# data_proV2.net
KiCad netlist of a schematic drawn in EAGLE
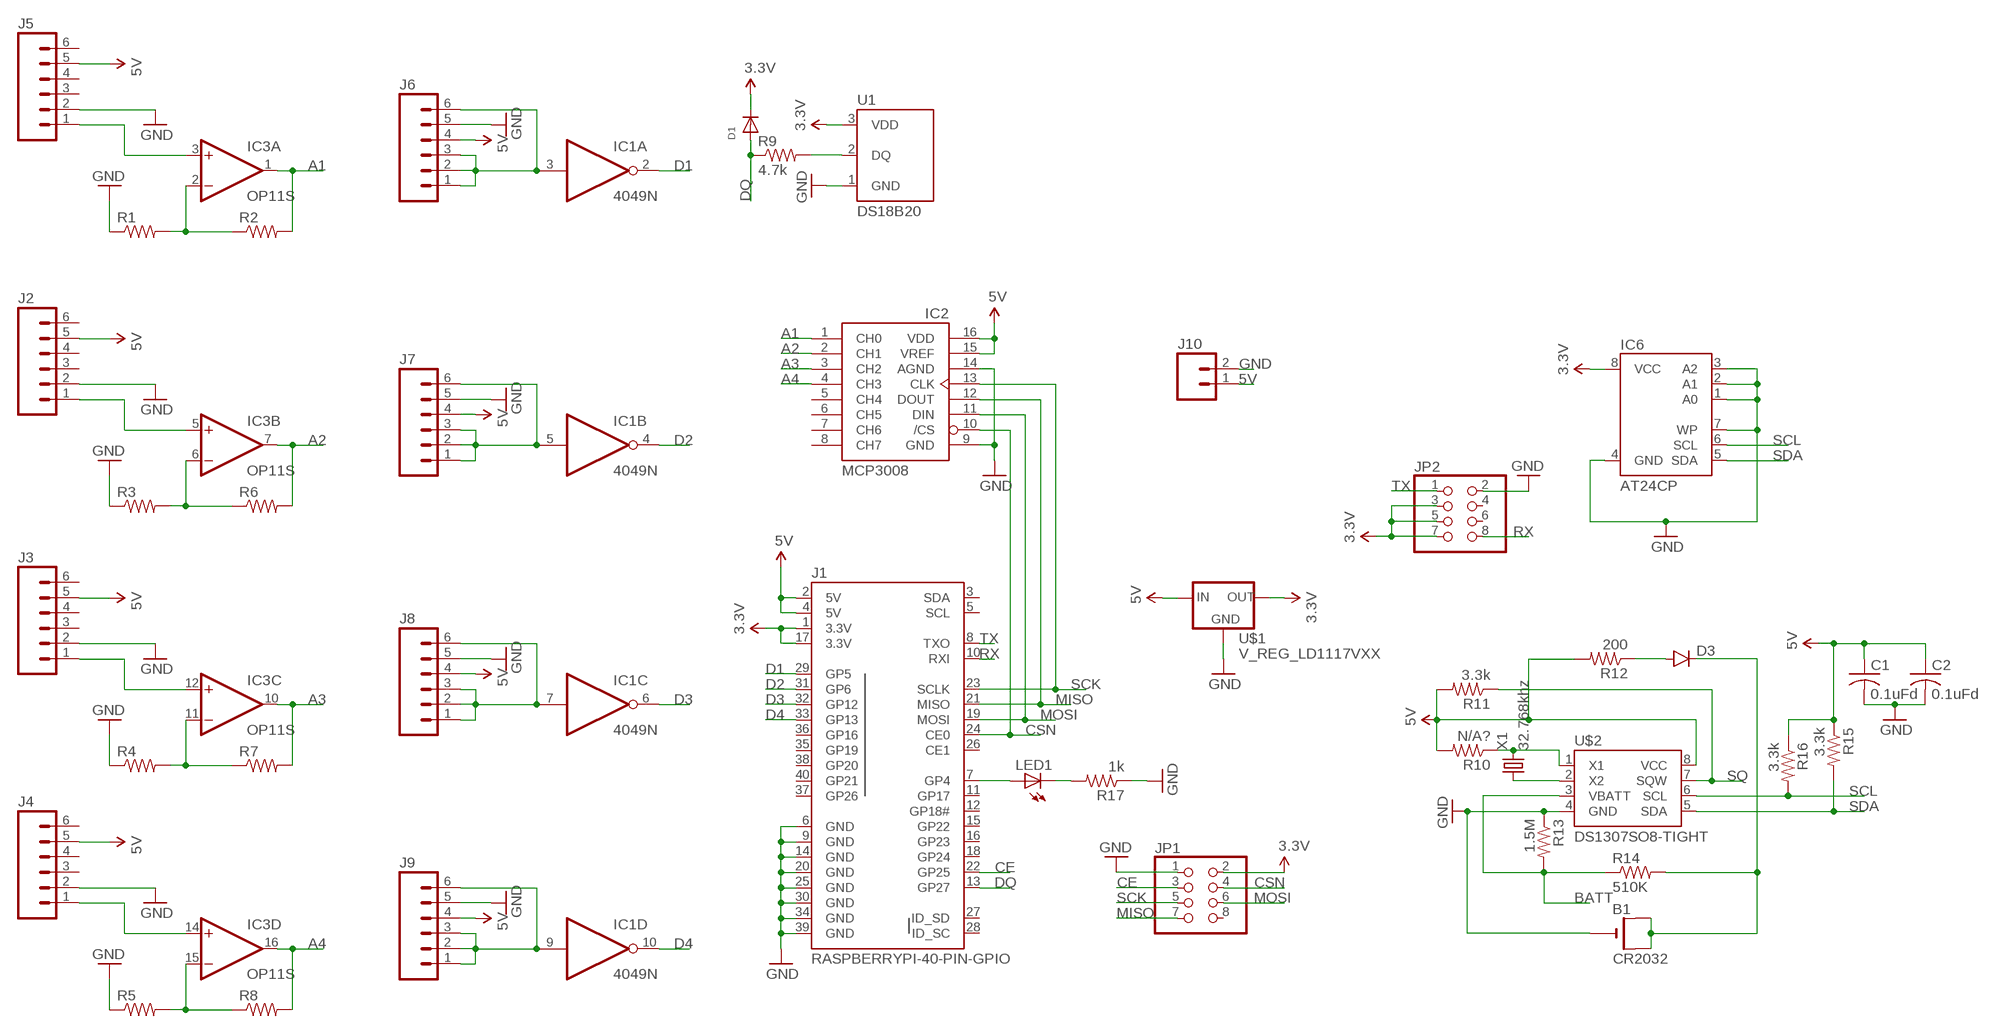
[diagram p0: schematic, sheet 1]

(export (version "E")
  (design (tool "Eeschema 10.0.6"))
  (components
    (comp (ref "B1")
      (value "CR2032")
      (footprint "eagle-import:CR2032-SMD")
      (libsource (lib "eagle-import") (part "CR2032SMT"))
    )
    (comp (ref "C1")
      (value "0.1uFd")
      (footprint "eagle-import:C0805")
      (libsource (lib "eagle-import") (part "C-USC0805"))
    )
    (comp (ref "C2")
      (value "0.1uFd")
      (footprint "eagle-import:C0805")
      (libsource (lib "eagle-import") (part "C-USC0805"))
    )
    (comp (ref "D1")
      (value "DIODESOD-323F")
      (footprint "eagle-import:SOD-323F")
      (libsource (lib "eagle-import") (part "DIODESOD-323F"))
    )
    (comp (ref "D3")
      (value "DIODESMB")
      (footprint "eagle-import:SMB-DIODE")
      (libsource (lib "eagle-import") (part "DIODESMB"))
    )
    (comp (ref "IC1")
      (value "4049N")
      (footprint "eagle-import:DIL16")
      (libsource (lib "eagle-import") (part "4049N"))
    )
    (comp (ref "IC2")
      (value "MCP3008")
      (footprint "eagle-import:DIL16")
      (libsource (lib "eagle-import") (part "MCP3008"))
    )
    (comp (ref "IC3")
      (value "OP11S")
      (footprint "eagle-import:DIL16")
      (libsource (lib "eagle-import") (part "OP11S"))
    )
    (comp (ref "IC6")
      (value "AT24CP")
      (footprint "eagle-import:DIL08")
      (fields (field (name "MPN") "AT24C1024BW-SH-B"))
      (libsource (lib "eagle-import") (part "AT24CP"))
    )
    (comp (ref "J1")
      (value "RASPBERRYPI-40-PIN-GPIO")
      (footprint "eagle-import:2X20-SHROUDED")
      (libsource (lib "eagle-import") (part "RASPBERRYPI-40-PIN-GPIO"))
    )
    (comp (ref "J2")
      (value "M06VERNIER-ANALOG")
      (footprint "eagle-import:BTA")
      (libsource (lib "eagle-import") (part "M06VERNIER-ANALOG"))
    )
    (comp (ref "J3")
      (value "M06VERNIER-ANALOG")
      (footprint "eagle-import:BTA")
      (libsource (lib "eagle-import") (part "M06VERNIER-ANALOG"))
    )
    (comp (ref "J4")
      (value "M06VERNIER-ANALOG")
      (footprint "eagle-import:BTA")
      (libsource (lib "eagle-import") (part "M06VERNIER-ANALOG"))
    )
    (comp (ref "J5")
      (value "M06VERNIER-ANALOG")
      (footprint "eagle-import:BTA")
      (libsource (lib "eagle-import") (part "M06VERNIER-ANALOG"))
    )
    (comp (ref "J6")
      (value "M06VERNIER-DIGITAL")
      (footprint "eagle-import:BTD")
      (libsource (lib "eagle-import") (part "M06VERNIER-DIGITAL"))
    )
    (comp (ref "J7")
      (value "M06VERNIER-DIGITAL")
      (footprint "eagle-import:BTD")
      (libsource (lib "eagle-import") (part "M06VERNIER-DIGITAL"))
    )
    (comp (ref "J8")
      (value "M06VERNIER-DIGITAL")
      (footprint "eagle-import:BTD")
      (libsource (lib "eagle-import") (part "M06VERNIER-DIGITAL"))
    )
    (comp (ref "J9")
      (value "M06VERNIER-DIGITAL")
      (footprint "eagle-import:BTD")
      (libsource (lib "eagle-import") (part "M06VERNIER-DIGITAL"))
    )
    (comp (ref "J10")
      (value "M02PTH")
      (footprint "eagle-import:1X02")
      (libsource (lib "eagle-import") (part "M02PTH"))
    )
    (comp (ref "JP1")
      (value "PINHD-2X4")
      (footprint "eagle-import:2X04")
      (libsource (lib "eagle-import") (part "pinhead_PINHD-2X4"))
    )
    (comp (ref "JP2")
      (value "PINHD-2X4")
      (footprint "eagle-import:2X04")
      (libsource (lib "eagle-import") (part "PINHD-2X4"))
    )
    (comp (ref "LED1")
      (value "LEDCHIP-LED0805")
      (footprint "eagle-import:CHIP-LED0805")
      (libsource (lib "eagle-import") (part "LEDCHIP-LED0805"))
    )
    (comp (ref "R1")
      (value "R-US_R0805")
      (footprint "eagle-import:R0805")
      (libsource (lib "eagle-import") (part "resistor_R-US_R0805"))
    )
    (comp (ref "R2")
      (value "R-US_R0805")
      (footprint "eagle-import:R0805")
      (libsource (lib "eagle-import") (part "resistor_R-US_R0805"))
    )
    (comp (ref "R3")
      (value "R-US_R0805")
      (footprint "eagle-import:R0805")
      (libsource (lib "eagle-import") (part "resistor_R-US_R0805"))
    )
    (comp (ref "R4")
      (value "R-US_R0805")
      (footprint "eagle-import:R0805")
      (libsource (lib "eagle-import") (part "resistor_R-US_R0805"))
    )
    (comp (ref "R5")
      (value "R-US_R0805")
      (footprint "eagle-import:R0805")
      (libsource (lib "eagle-import") (part "resistor_R-US_R0805"))
    )
    (comp (ref "R6")
      (value "R-US_R0805")
      (footprint "eagle-import:R0805")
      (libsource (lib "eagle-import") (part "resistor_R-US_R0805"))
    )
    (comp (ref "R7")
      (value "R-US_R0805")
      (footprint "eagle-import:R0805")
      (libsource (lib "eagle-import") (part "resistor_R-US_R0805"))
    )
    (comp (ref "R8")
      (value "R-US_R0805")
      (footprint "eagle-import:R0805")
      (libsource (lib "eagle-import") (part "resistor_R-US_R0805"))
    )
    (comp (ref "R9")
      (value "4.7k")
      (footprint "eagle-import:R0805")
      (libsource (lib "eagle-import") (part "resistor_R-US_R0805"))
    )
    (comp (ref "R10")
      (value "N/A?")
      (footprint "eagle-import:R0805")
      (libsource (lib "eagle-import") (part "R-US_R0805"))
    )
    (comp (ref "R11")
      (value "3.3k")
      (footprint "eagle-import:R0805")
      (libsource (lib "eagle-import") (part "R-US_R0805"))
    )
    (comp (ref "R12")
      (value "200")
      (footprint "eagle-import:R0805")
      (libsource (lib "eagle-import") (part "R-US_R0805"))
    )
    (comp (ref "R13")
      (value "1.5M")
      (footprint "eagle-import:R0805")
      (libsource (lib "eagle-import") (part "R-US_R0805"))
    )
    (comp (ref "R14")
      (value "510K")
      (footprint "eagle-import:R0805")
      (libsource (lib "eagle-import") (part "R-US_R0805"))
    )
    (comp (ref "R15")
      (value "3.3k")
      (footprint "eagle-import:R0805")
      (libsource (lib "eagle-import") (part "R-US_R0805"))
    )
    (comp (ref "R16")
      (value "3.3k")
      (footprint "eagle-import:R0805")
      (libsource (lib "eagle-import") (part "R-US_R0805"))
    )
    (comp (ref "R17")
      (value "1k")
      (footprint "eagle-import:R0805")
      (libsource (lib "eagle-import") (part "R-US_R0805"))
    )
    (comp (ref "U$1")
      (value "V_REG_LD1117VXX")
      (footprint "eagle-import:78XXL")
      (libsource (lib "eagle-import") (part "V_REG_LD1117VXX"))
    )
    (comp (ref "U$2")
      (value "DS1307SO8-TIGHT")
      (footprint "eagle-import:SO08-TIGHT")
      (libsource (lib "eagle-import") (part "DS1307SO8-TIGHT"))
    )
    (comp (ref "U1")
      (value "DS18B20")
      (footprint "eagle-import:TO-92-AMMO")
      (libsource (lib "eagle-import") (part "DS18B20"))
    )
    (comp (ref "X1")
      (value "32.768khz")
      (footprint "eagle-import:TC38H")
      (libsource (lib "eagle-import") (part "CRYSTALTC38H"))
    )
  )
  (nets
    (net (code "1") (name "/A1") (class "Default")
      (node (ref "IC2") (pin "1") (pinfunction "CH0_1") (pintype "input"))
      (node (ref "IC3") (pin "1") (pinfunction "OUT_1") (pintype "output"))
      (node (ref "R2") (pin "2") (pinfunction "2_2") (pintype "passive"))
    )
    (net (code "2") (name "/A2") (class "Default")
      (node (ref "IC2") (pin "2") (pinfunction "CH1_2") (pintype "input"))
      (node (ref "IC3") (pin "7") (pinfunction "OUT_7") (pintype "output"))
      (node (ref "R6") (pin "2") (pinfunction "2_2") (pintype "passive"))
    )
    (net (code "3") (name "/A3") (class "Default")
      (node (ref "IC2") (pin "3") (pinfunction "CH2_3") (pintype "input"))
      (node (ref "IC3") (pin "10") (pinfunction "OUT_10") (pintype "output"))
      (node (ref "R7") (pin "2") (pinfunction "2_2") (pintype "passive"))
    )
    (net (code "4") (name "/A4") (class "Default")
      (node (ref "IC2") (pin "4") (pinfunction "CH3_4") (pintype "input"))
      (node (ref "IC3") (pin "16") (pinfunction "OUT_16") (pintype "output"))
      (node (ref "R8") (pin "2") (pinfunction "2_2") (pintype "passive"))
    )
    (net (code "5") (name "/BATT") (class "Default")
      (node (ref "R13") (pin "2") (pinfunction "2_2") (pintype "passive"))
      (node (ref "R14") (pin "1") (pinfunction "1_1") (pintype "passive"))
      (node (ref "U$2") (pin "3") (pinfunction "VBATT_3") (pintype "bidirectional"))
    )
    (net (code "6") (name "/CE") (class "Default")
      (node (ref "J1") (pin "22") (pinfunction "GP25_22") (pintype "bidirectional"))
      (node (ref "JP1") (pin "3") (pinfunction "3_3") (pintype "passive"))
    )
    (net (code "7") (name "/CSN") (class "Default")
      (node (ref "IC2") (pin "10") (pinfunction "/CS_10") (pintype "input"))
      (node (ref "J1") (pin "24") (pinfunction "CE0_24") (pintype "output"))
      (node (ref "JP1") (pin "4") (pinfunction "4_4") (pintype "passive"))
    )
    (net (code "8") (name "/D1") (class "Default")
      (node (ref "IC1") (pin "2") (pinfunction "O_2") (pintype "output"))
      (node (ref "J1") (pin "29") (pinfunction "GP5_29") (pintype "bidirectional"))
    )
    (net (code "9") (name "/D2") (class "Default")
      (node (ref "IC1") (pin "4") (pinfunction "O_4") (pintype "output"))
      (node (ref "J1") (pin "31") (pinfunction "GP6_31") (pintype "bidirectional"))
    )
    (net (code "10") (name "/D3") (class "Default")
      (node (ref "IC1") (pin "6") (pinfunction "O_6") (pintype "output"))
      (node (ref "J1") (pin "32") (pinfunction "GP12_32") (pintype "bidirectional"))
    )
    (net (code "11") (name "/D4") (class "Default")
      (node (ref "IC1") (pin "10") (pinfunction "O_10") (pintype "output"))
      (node (ref "J1") (pin "33") (pinfunction "GP13_33") (pintype "bidirectional"))
    )
    (net (code "12") (name "/DQ") (class "Default")
      (node (ref "D1") (pin "A") (pinfunction "A_A") (pintype "passive"))
      (node (ref "J1") (pin "13") (pinfunction "GP27_13") (pintype "bidirectional"))
      (node (ref "R9") (pin "1") (pinfunction "1_1") (pintype "passive"))
    )
    (net (code "13") (name "/MISO") (class "Default")
      (node (ref "IC2") (pin "12") (pinfunction "DOUT_12") (pintype "output"))
      (node (ref "J1") (pin "21") (pinfunction "MISO_21") (pintype "input"))
      (node (ref "JP1") (pin "7") (pinfunction "7_7") (pintype "passive"))
    )
    (net (code "14") (name "/MOSI") (class "Default")
      (node (ref "IC2") (pin "11") (pinfunction "DIN_11") (pintype "input"))
      (node (ref "J1") (pin "19") (pinfunction "MOSI_19") (pintype "output"))
      (node (ref "JP1") (pin "6") (pinfunction "6_6") (pintype "passive"))
    )
    (net (code "15") (name "/RX") (class "Default")
      (node (ref "J1") (pin "10") (pinfunction "RXI_10") (pintype "input"))
      (node (ref "JP2") (pin "8") (pinfunction "8_8") (pintype "passive"))
    )
    (net (code "16") (name "/SCK") (class "Default")
      (node (ref "IC2") (pin "13") (pinfunction "CLK_13") (pintype "input"))
      (node (ref "J1") (pin "23") (pinfunction "SCLK_23") (pintype "output"))
      (node (ref "JP1") (pin "5") (pinfunction "5_5") (pintype "passive"))
    )
    (net (code "17") (name "/SCL") (class "Default")
      (node (ref "IC6") (pin "6") (pinfunction "SCL_6") (pintype "bidirectional"))
      (node (ref "R16") (pin "2") (pinfunction "2_2") (pintype "passive"))
      (node (ref "U$2") (pin "6") (pinfunction "SCL_6") (pintype "bidirectional"))
    )
    (net (code "18") (name "/SDA") (class "Default")
      (node (ref "IC6") (pin "5") (pinfunction "SDA_5") (pintype "bidirectional"))
      (node (ref "R15") (pin "2") (pinfunction "2_2") (pintype "passive"))
      (node (ref "U$2") (pin "5") (pinfunction "SDA_5") (pintype "bidirectional"))
    )
    (net (code "19") (name "/SQ") (class "Default")
      (node (ref "R11") (pin "1") (pinfunction "1_1") (pintype "passive"))
      (node (ref "U$2") (pin "7") (pinfunction "SQW_7") (pintype "bidirectional"))
    )
    (net (code "20") (name "/TX") (class "Default")
      (node (ref "J1") (pin "8") (pinfunction "TXO_8") (pintype "output"))
      (node (ref "JP2") (pin "1") (pinfunction "1_1") (pintype "passive"))
    )
    (net (code "21") (name "3.3V") (class "Default")
      (node (ref "D1") (pin "C") (pinfunction "C_C") (pintype "passive"))
      (node (ref "IC6") (pin "8") (pinfunction "VCC_8") (pintype "power_in"))
      (node (ref "J1") (pin "1") (pinfunction "3.3V_1") (pintype "power_in"))
      (node (ref "J1") (pin "17") (pinfunction "3.3V_17") (pintype "power_in"))
      (node (ref "JP1") (pin "2") (pinfunction "2_2") (pintype "passive"))
      (node (ref "JP2") (pin "3") (pinfunction "3_3") (pintype "passive"))
      (node (ref "JP2") (pin "5") (pinfunction "5_5") (pintype "passive"))
      (node (ref "JP2") (pin "7") (pinfunction "7_7") (pintype "passive"))
      (node (ref "U$1") (pin "GND") (pinfunction "OUT_GND") (pintype "passive"))
      (node (ref "U1") (pin "3") (pinfunction "VDD_3") (pintype "power_in"))
    )
    (net (code "22") (name "5V") (class "Default")
      (node (ref "C1") (pin "1") (pinfunction "1_1") (pintype "passive"))
      (node (ref "C2") (pin "1") (pinfunction "1_1") (pintype "passive"))
      (node (ref "IC2") (pin "15") (pinfunction "VREF_15") (pintype "input"))
      (node (ref "IC2") (pin "16") (pinfunction "VDD_16") (pintype "power_in"))
      (node (ref "J1") (pin "2") (pinfunction "5V_2") (pintype "power_in"))
      (node (ref "J1") (pin "4") (pinfunction "5V_4") (pintype "power_in"))
      (node (ref "J10") (pin "1") (pinfunction "1_1") (pintype "passive"))
      (node (ref "J2") (pin "5") (pinfunction "5_5") (pintype "passive"))
      (node (ref "J3") (pin "5") (pinfunction "5_5") (pintype "passive"))
      (node (ref "J4") (pin "5") (pinfunction "5_5") (pintype "passive"))
      (node (ref "J5") (pin "5") (pinfunction "5_5") (pintype "passive"))
      (node (ref "J6") (pin "4") (pinfunction "4_4") (pintype "passive"))
      (node (ref "J7") (pin "4") (pinfunction "4_4") (pintype "passive"))
      (node (ref "J8") (pin "4") (pinfunction "4_4") (pintype "passive"))
      (node (ref "J9") (pin "4") (pinfunction "4_4") (pintype "passive"))
      (node (ref "R10") (pin "2") (pinfunction "2_2") (pintype "passive"))
      (node (ref "R11") (pin "2") (pinfunction "2_2") (pintype "passive"))
      (node (ref "R12") (pin "2") (pinfunction "2_2") (pintype "passive"))
      (node (ref "R15") (pin "1") (pinfunction "1_1") (pintype "passive"))
      (node (ref "R16") (pin "1") (pinfunction "1_1") (pintype "passive"))
      (node (ref "U$1") (pin "OUT") (pinfunction "IN_OUT") (pintype "input"))
      (node (ref "U$2") (pin "8") (pinfunction "VCC_8") (pintype "bidirectional"))
    )
    (net (code "23") (name "GND") (class "Default")
      (node (ref "B1") (pin "-") (pinfunction "-_-") (pintype "passive"))
      (node (ref "C1") (pin "2") (pinfunction "2_2") (pintype "passive"))
      (node (ref "C2") (pin "2") (pinfunction "2_2") (pintype "passive"))
      (node (ref "IC2") (pin "14") (pinfunction "AGND_14") (pintype "power_in"))
      (node (ref "IC2") (pin "9") (pinfunction "GND_9") (pintype "power_in"))
      (node (ref "IC6") (pin "1") (pinfunction "A0_1") (pintype "input"))
      (node (ref "IC6") (pin "2") (pinfunction "A1_2") (pintype "input"))
      (node (ref "IC6") (pin "3") (pinfunction "A2_3") (pintype "input"))
      (node (ref "IC6") (pin "4") (pinfunction "GND_4") (pintype "power_in"))
      (node (ref "IC6") (pin "7") (pinfunction "WP_7") (pintype "input"))
      (node (ref "J1") (pin "14") (pinfunction "GND_14") (pintype "power_in"))
      (node (ref "J1") (pin "20") (pinfunction "GND_20") (pintype "power_in"))
      (node (ref "J1") (pin "25") (pinfunction "GND_25") (pintype "power_in"))
      (node (ref "J1") (pin "30") (pinfunction "GND_30") (pintype "power_in"))
      (node (ref "J1") (pin "34") (pinfunction "GND_34") (pintype "power_in"))
      (node (ref "J1") (pin "39") (pinfunction "GND_39") (pintype "power_in"))
      (node (ref "J1") (pin "6") (pinfunction "GND_6") (pintype "power_in"))
      (node (ref "J1") (pin "9") (pinfunction "GND_9") (pintype "power_in"))
      (node (ref "J10") (pin "2") (pinfunction "2_2") (pintype "passive"))
      (node (ref "J2") (pin "2") (pinfunction "2_2") (pintype "passive"))
      (node (ref "J3") (pin "2") (pinfunction "2_2") (pintype "passive"))
      (node (ref "J4") (pin "2") (pinfunction "2_2") (pintype "passive"))
      (node (ref "J5") (pin "2") (pinfunction "2_2") (pintype "passive"))
      (node (ref "J6") (pin "5") (pinfunction "5_5") (pintype "passive"))
      (node (ref "J7") (pin "5") (pinfunction "5_5") (pintype "passive"))
      (node (ref "J8") (pin "5") (pinfunction "5_5") (pintype "passive"))
      (node (ref "J9") (pin "5") (pinfunction "5_5") (pintype "passive"))
      (node (ref "JP1") (pin "1") (pinfunction "1_1") (pintype "passive"))
      (node (ref "JP2") (pin "2") (pinfunction "2_2") (pintype "passive"))
      (node (ref "R1") (pin "1") (pinfunction "1_1") (pintype "passive"))
      (node (ref "R13") (pin "1") (pinfunction "1_1") (pintype "passive"))
      (node (ref "R17") (pin "1") (pinfunction "1_1") (pintype "passive"))
      (node (ref "R3") (pin "1") (pinfunction "1_1") (pintype "passive"))
      (node (ref "R4") (pin "1") (pinfunction "1_1") (pintype "passive"))
      (node (ref "R5") (pin "1") (pinfunction "1_1") (pintype "passive"))
      (node (ref "U$1") (pin "IN") (pinfunction "GND_IN") (pintype "input"))
      (node (ref "U$2") (pin "4") (pinfunction "GND_4") (pintype "bidirectional"))
      (node (ref "U1") (pin "1") (pinfunction "GND_1") (pintype "power_in"))
    )
    (net (code "24") (name "Net-(B1-+)") (class "Default")
      (node (ref "B1") (pin "+$1") (pinfunction "+_+$1") (pintype "passive"))
      (node (ref "B1") (pin "+$2") (pinfunction "+1_+$2") (pintype "passive"))
      (node (ref "D3") (pin "C") (pinfunction "C_C") (pintype "passive"))
      (node (ref "R14") (pin "2") (pinfunction "2_2") (pintype "passive"))
    )
    (net (code "25") (name "Net-(D3-PadA)") (class "Default")
      (node (ref "D3") (pin "A") (pinfunction "A_A") (pintype "passive"))
      (node (ref "R12") (pin "1") (pinfunction "1_1") (pintype "passive"))
    )
    (net (code "26") (name "Net-(IC1A-I)") (class "Default")
      (node (ref "IC1") (pin "3") (pinfunction "I_3") (pintype "input"))
      (node (ref "J6") (pin "1") (pinfunction "1_1") (pintype "passive"))
      (node (ref "J6") (pin "2") (pinfunction "2_2") (pintype "passive"))
      (node (ref "J6") (pin "3") (pinfunction "3_3") (pintype "passive"))
      (node (ref "J6") (pin "6") (pinfunction "6_6") (pintype "passive"))
    )
    (net (code "27") (name "Net-(IC1B-I)") (class "Default")
      (node (ref "IC1") (pin "5") (pinfunction "I_5") (pintype "input"))
      (node (ref "J7") (pin "1") (pinfunction "1_1") (pintype "passive"))
      (node (ref "J7") (pin "2") (pinfunction "2_2") (pintype "passive"))
      (node (ref "J7") (pin "3") (pinfunction "3_3") (pintype "passive"))
      (node (ref "J7") (pin "6") (pinfunction "6_6") (pintype "passive"))
    )
    (net (code "28") (name "Net-(IC1C-I)") (class "Default")
      (node (ref "IC1") (pin "7") (pinfunction "I_7") (pintype "input"))
      (node (ref "J8") (pin "1") (pinfunction "1_1") (pintype "passive"))
      (node (ref "J8") (pin "2") (pinfunction "2_2") (pintype "passive"))
      (node (ref "J8") (pin "3") (pinfunction "3_3") (pintype "passive"))
      (node (ref "J8") (pin "6") (pinfunction "6_6") (pintype "passive"))
    )
    (net (code "29") (name "Net-(IC1D-I)") (class "Default")
      (node (ref "IC1") (pin "9") (pinfunction "I_9") (pintype "input"))
      (node (ref "J9") (pin "1") (pinfunction "1_1") (pintype "passive"))
      (node (ref "J9") (pin "2") (pinfunction "2_2") (pintype "passive"))
      (node (ref "J9") (pin "3") (pinfunction "3_3") (pintype "passive"))
      (node (ref "J9") (pin "6") (pinfunction "6_6") (pintype "passive"))
    )
    (net (code "30") (name "Net-(IC3A-+IN)") (class "Default")
      (node (ref "IC3") (pin "3") (pinfunction "+IN_3") (pintype "input"))
      (node (ref "J5") (pin "1") (pinfunction "1_1") (pintype "passive"))
    )
    (net (code "31") (name "Net-(IC3A--IN)") (class "Default")
      (node (ref "IC3") (pin "2") (pinfunction "-IN_2") (pintype "input"))
      (node (ref "R1") (pin "2") (pinfunction "2_2") (pintype "passive"))
      (node (ref "R2") (pin "1") (pinfunction "1_1") (pintype "passive"))
    )
    (net (code "32") (name "Net-(IC3B-+IN)") (class "Default")
      (node (ref "IC3") (pin "5") (pinfunction "+IN_5") (pintype "input"))
      (node (ref "J2") (pin "1") (pinfunction "1_1") (pintype "passive"))
    )
    (net (code "33") (name "Net-(IC3B--IN)") (class "Default")
      (node (ref "IC3") (pin "6") (pinfunction "-IN_6") (pintype "input"))
      (node (ref "R3") (pin "2") (pinfunction "2_2") (pintype "passive"))
      (node (ref "R6") (pin "1") (pinfunction "1_1") (pintype "passive"))
    )
    (net (code "34") (name "Net-(IC3C-+IN)") (class "Default")
      (node (ref "IC3") (pin "12") (pinfunction "+IN_12") (pintype "input"))
      (node (ref "J3") (pin "1") (pinfunction "1_1") (pintype "passive"))
    )
    (net (code "35") (name "Net-(IC3C--IN)") (class "Default")
      (node (ref "IC3") (pin "11") (pinfunction "-IN_11") (pintype "input"))
      (node (ref "R4") (pin "2") (pinfunction "2_2") (pintype "passive"))
      (node (ref "R7") (pin "1") (pinfunction "1_1") (pintype "passive"))
    )
    (net (code "36") (name "Net-(IC3D-+IN)") (class "Default")
      (node (ref "IC3") (pin "14") (pinfunction "+IN_14") (pintype "input"))
      (node (ref "J4") (pin "1") (pinfunction "1_1") (pintype "passive"))
    )
    (net (code "37") (name "Net-(IC3D--IN)") (class "Default")
      (node (ref "IC3") (pin "15") (pinfunction "-IN_15") (pintype "input"))
      (node (ref "R5") (pin "2") (pinfunction "2_2") (pintype "passive"))
      (node (ref "R8") (pin "1") (pinfunction "1_1") (pintype "passive"))
    )
    (net (code "38") (name "Net-(J1-GP4)") (class "Default")
      (node (ref "J1") (pin "7") (pinfunction "GP4_7") (pintype "bidirectional"))
      (node (ref "LED1") (pin "A") (pinfunction "A_A") (pintype "passive"))
    )
    (net (code "39") (name "Net-(LED1-PadC)") (class "Default")
      (node (ref "LED1") (pin "C") (pinfunction "C_C") (pintype "passive"))
      (node (ref "R17") (pin "2") (pinfunction "2_2") (pintype "passive"))
    )
    (net (code "40") (name "Net-(U$2-X1)") (class "Default")
      (node (ref "R10") (pin "1") (pinfunction "1_1") (pintype "passive"))
      (node (ref "U$2") (pin "1") (pinfunction "X1_1") (pintype "bidirectional"))
      (node (ref "X1") (pin "2") (pinfunction "2_2") (pintype "passive"))
    )
    (net (code "41") (name "Net-(U$2-X2)") (class "Default")
      (node (ref "U$2") (pin "2") (pinfunction "X2_2") (pintype "bidirectional"))
      (node (ref "X1") (pin "1") (pinfunction "1_1") (pintype "passive"))
    )
    (net (code "42") (name "Net-(U1-DQ)") (class "Default")
      (node (ref "R9") (pin "2") (pinfunction "2_2") (pintype "passive"))
      (node (ref "U1") (pin "2") (pinfunction "DQ_2") (pintype "bidirectional"))
    )
    (net (code "43") (name "unconnected-(IC2-CH4-Pad5)") (class "Default")
      (node (ref "IC2") (pin "5") (pinfunction "CH4_5") (pintype "input"))
    )
    (net (code "44") (name "unconnected-(IC2-CH5-Pad6)") (class "Default")
      (node (ref "IC2") (pin "6") (pinfunction "CH5_6") (pintype "input"))
    )
    (net (code "45") (name "unconnected-(IC2-CH6-Pad7)") (class "Default")
      (node (ref "IC2") (pin "7") (pinfunction "CH6_7") (pintype "input"))
    )
    (net (code "46") (name "unconnected-(IC2-CH7-Pad8)") (class "Default")
      (node (ref "IC2") (pin "8") (pinfunction "CH7_8") (pintype "input"))
    )
    (net (code "47") (name "unconnected-(J1-CE1-Pad26)") (class "Default")
      (node (ref "J1") (pin "26") (pinfunction "CE1_26") (pintype "output"))
    )
    (net (code "48") (name "unconnected-(J1-GP16-Pad36)") (class "Default")
      (node (ref "J1") (pin "36") (pinfunction "GP16_36") (pintype "bidirectional"))
    )
    (net (code "49") (name "unconnected-(J1-GP17-Pad11)") (class "Default")
      (node (ref "J1") (pin "11") (pinfunction "GP17_11") (pintype "bidirectional"))
    )
    (net (code "50") (name "unconnected-(J1-GP18#-Pad12)") (class "Default")
      (node (ref "J1") (pin "12") (pinfunction "GP18#_12") (pintype "bidirectional"))
    )
    (net (code "51") (name "unconnected-(J1-GP19-Pad35)") (class "Default")
      (node (ref "J1") (pin "35") (pinfunction "GP19_35") (pintype "bidirectional"))
    )
    (net (code "52") (name "unconnected-(J1-GP20-Pad38)") (class "Default")
      (node (ref "J1") (pin "38") (pinfunction "GP20_38") (pintype "bidirectional"))
    )
    (net (code "53") (name "unconnected-(J1-GP21-Pad40)") (class "Default")
      (node (ref "J1") (pin "40") (pinfunction "GP21_40") (pintype "bidirectional"))
    )
    (net (code "54") (name "unconnected-(J1-GP22-Pad15)") (class "Default")
      (node (ref "J1") (pin "15") (pinfunction "GP22_15") (pintype "bidirectional"))
    )
    (net (code "55") (name "unconnected-(J1-GP23-Pad16)") (class "Default")
      (node (ref "J1") (pin "16") (pinfunction "GP23_16") (pintype "bidirectional"))
    )
    (net (code "56") (name "unconnected-(J1-GP24-Pad18)") (class "Default")
      (node (ref "J1") (pin "18") (pinfunction "GP24_18") (pintype "bidirectional"))
    )
    (net (code "57") (name "unconnected-(J1-GP26-Pad37)") (class "Default")
      (node (ref "J1") (pin "37") (pinfunction "GP26_37") (pintype "bidirectional"))
    )
    (net (code "58") (name "unconnected-(J1-ID_SC-Pad28)") (class "Default")
      (node (ref "J1") (pin "28") (pinfunction "ID_SC_28") (pintype "bidirectional"))
    )
    (net (code "59") (name "unconnected-(J1-ID_SD-Pad27)") (class "Default")
      (node (ref "J1") (pin "27") (pinfunction "ID_SD_27") (pintype "bidirectional"))
    )
    (net (code "60") (name "unconnected-(J1-SCL-Pad5)") (class "Default")
      (node (ref "J1") (pin "5") (pinfunction "SCL_5") (pintype "bidirectional"))
    )
    (net (code "61") (name "unconnected-(J1-SDA-Pad3)") (class "Default")
      (node (ref "J1") (pin "3") (pinfunction "SDA_3") (pintype "bidirectional"))
    )
    (net (code "62") (name "unconnected-(J2-Pad3)") (class "Default")
      (node (ref "J2") (pin "3") (pinfunction "3_3") (pintype "passive"))
    )
    (net (code "63") (name "unconnected-(J2-Pad4)") (class "Default")
      (node (ref "J2") (pin "4") (pinfunction "4_4") (pintype "passive"))
    )
    (net (code "64") (name "unconnected-(J2-Pad6)") (class "Default")
      (node (ref "J2") (pin "6") (pinfunction "6_6") (pintype "passive"))
    )
    (net (code "65") (name "unconnected-(J3-Pad3)") (class "Default")
      (node (ref "J3") (pin "3") (pinfunction "3_3") (pintype "passive"))
    )
    (net (code "66") (name "unconnected-(J3-Pad4)") (class "Default")
      (node (ref "J3") (pin "4") (pinfunction "4_4") (pintype "passive"))
    )
    (net (code "67") (name "unconnected-(J3-Pad6)") (class "Default")
      (node (ref "J3") (pin "6") (pinfunction "6_6") (pintype "passive"))
    )
    (net (code "68") (name "unconnected-(J4-Pad3)") (class "Default")
      (node (ref "J4") (pin "3") (pinfunction "3_3") (pintype "passive"))
    )
    (net (code "69") (name "unconnected-(J4-Pad4)") (class "Default")
      (node (ref "J4") (pin "4") (pinfunction "4_4") (pintype "passive"))
    )
    (net (code "70") (name "unconnected-(J4-Pad6)") (class "Default")
      (node (ref "J4") (pin "6") (pinfunction "6_6") (pintype "passive"))
    )
    (net (code "71") (name "unconnected-(J5-Pad3)") (class "Default")
      (node (ref "J5") (pin "3") (pinfunction "3_3") (pintype "passive"))
    )
    (net (code "72") (name "unconnected-(J5-Pad4)") (class "Default")
      (node (ref "J5") (pin "4") (pinfunction "4_4") (pintype "passive"))
    )
    (net (code "73") (name "unconnected-(J5-Pad6)") (class "Default")
      (node (ref "J5") (pin "6") (pinfunction "6_6") (pintype "passive"))
    )
    (net (code "74") (name "unconnected-(JP1-Pad8)") (class "Default")
      (node (ref "JP1") (pin "8") (pinfunction "8_8") (pintype "passive"))
    )
    (net (code "75") (name "unconnected-(JP2-Pad4)") (class "Default")
      (node (ref "JP2") (pin "4") (pinfunction "4_4") (pintype "passive"))
    )
    (net (code "76") (name "unconnected-(JP2-Pad6)") (class "Default")
      (node (ref "JP2") (pin "6") (pinfunction "6_6") (pintype "passive"))
    )
  )
)
